# 2022-11-04_ESP32-Cseries_Riser.net
KiCad netlist of a schematic drawn in EasyEDA
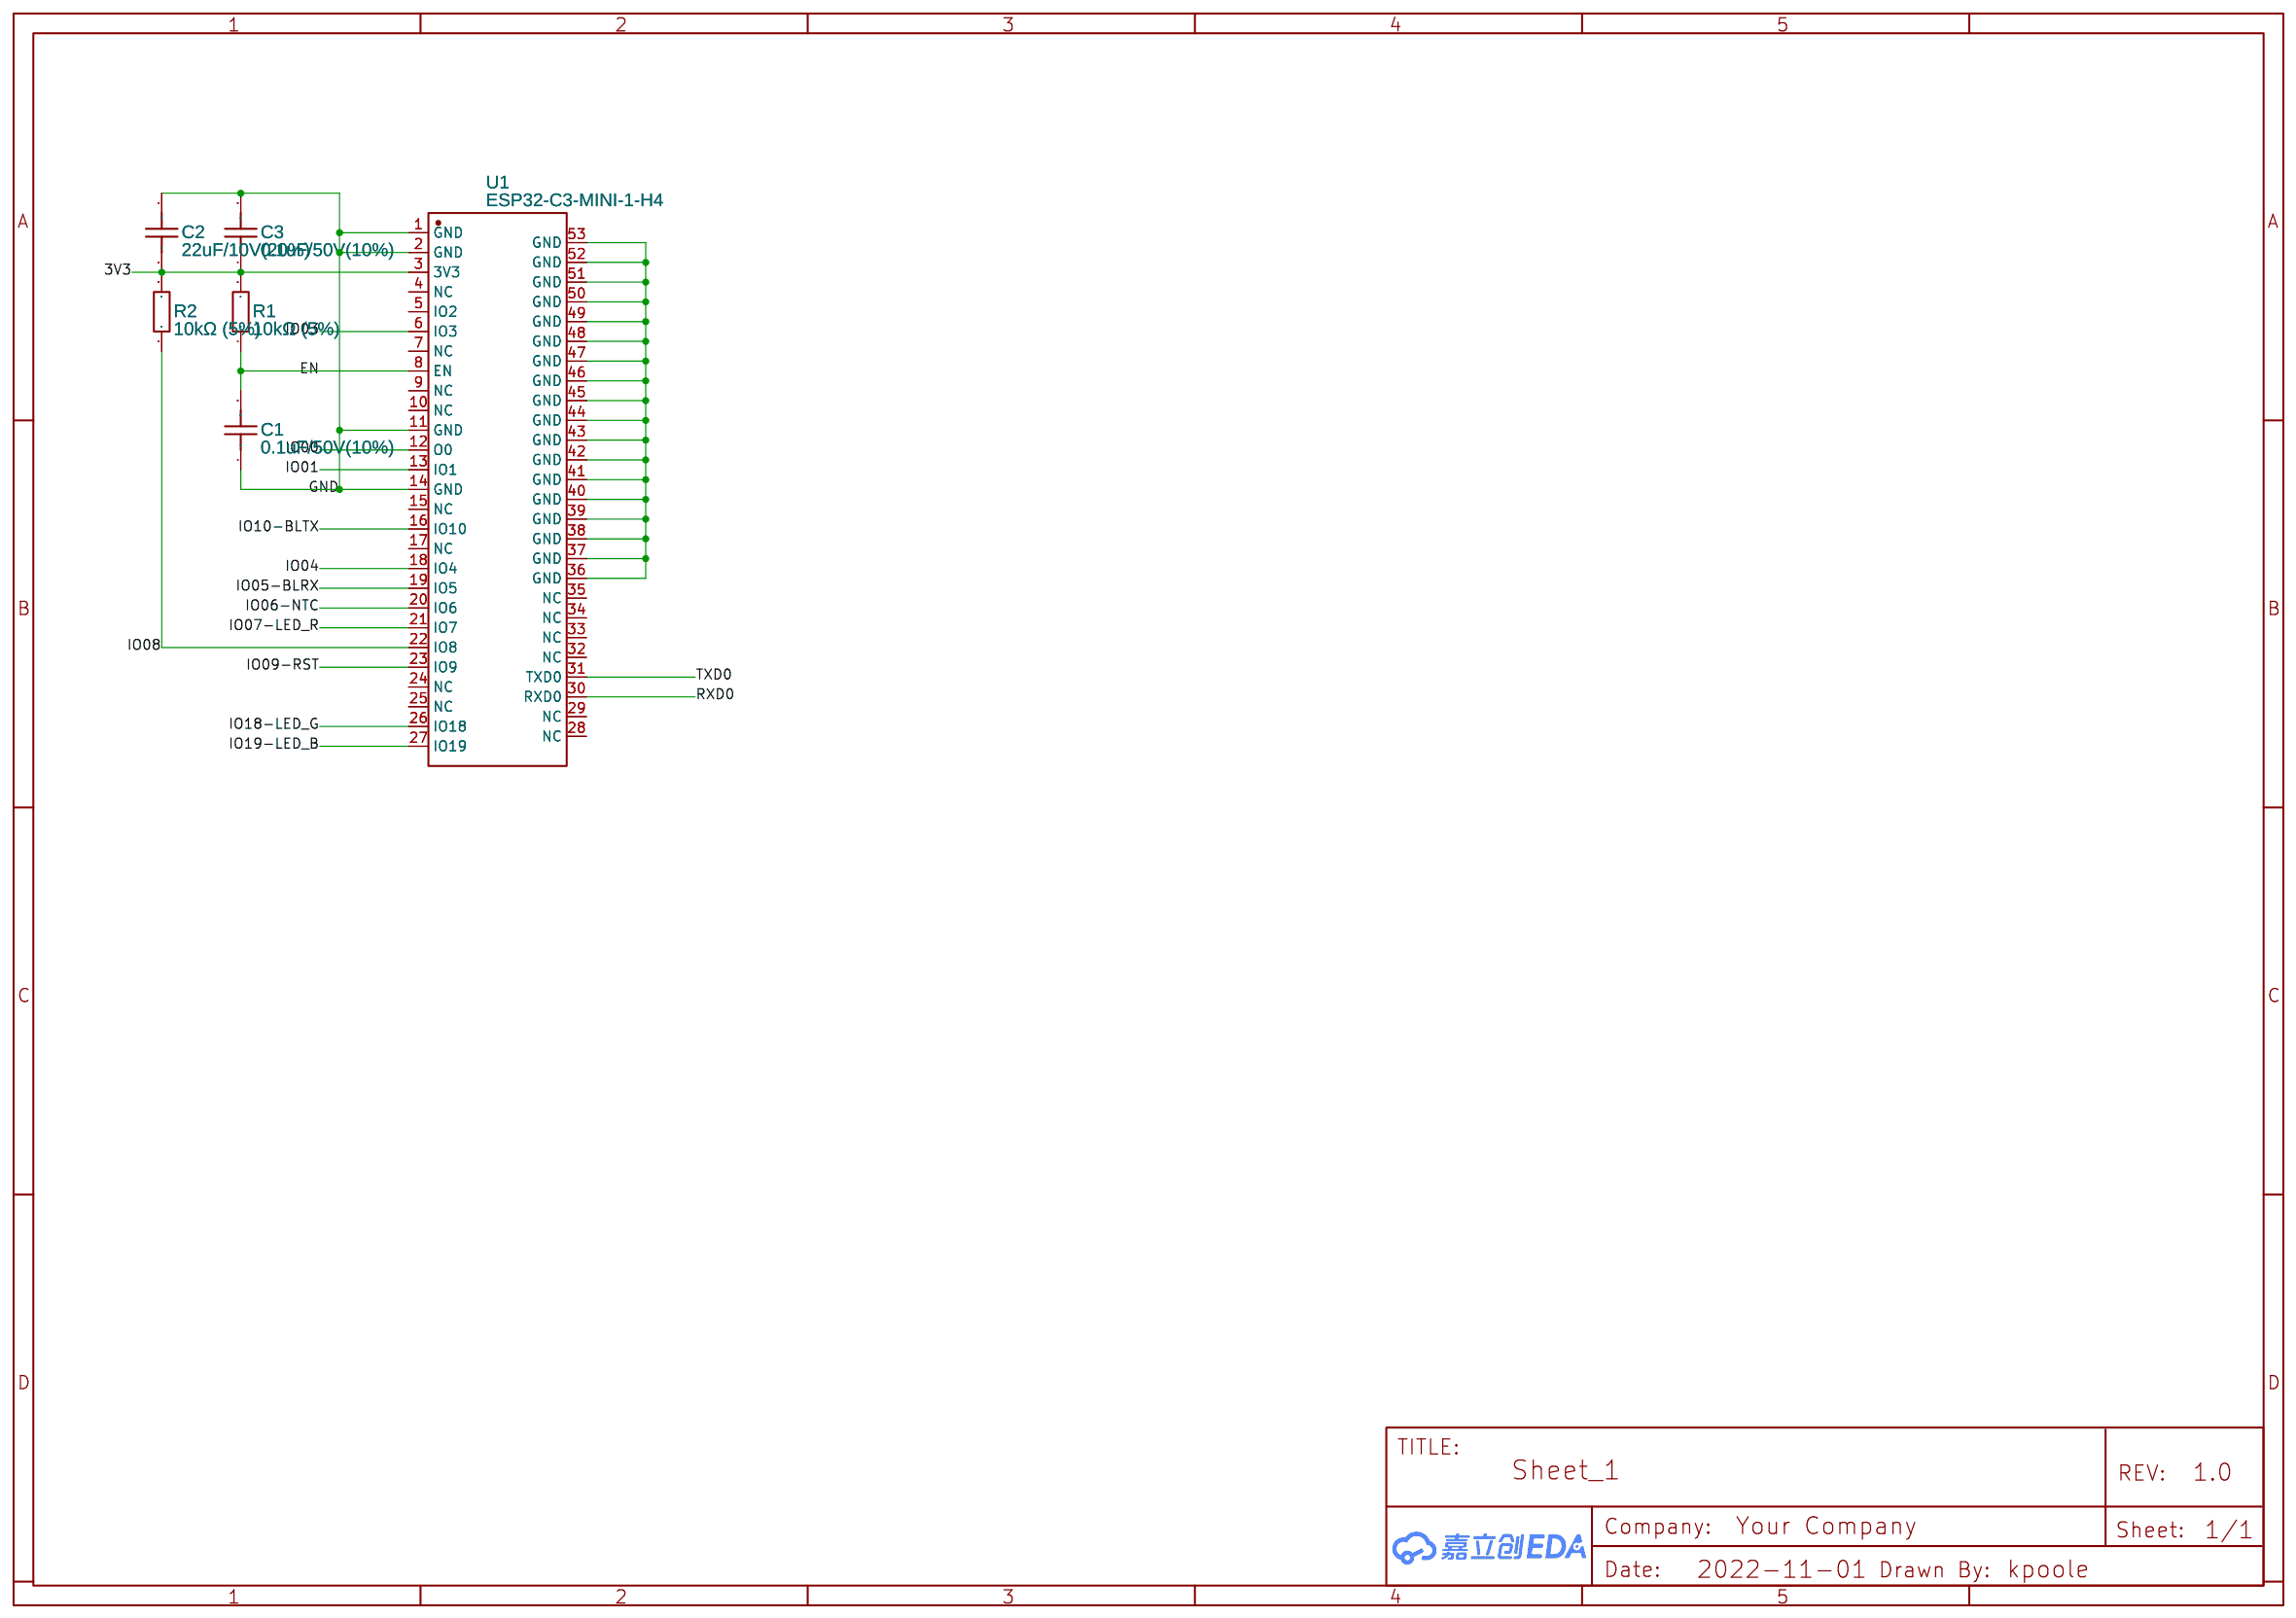
[diagram p0: schematic sheet]

(export (version "E")
  (design (tool "Eeschema 10.0.6"))
  (components
    (comp (ref "C1")
      (value "0.1uF/50V(10%)")
      (fields
        (field (name "BOM_Manufacturer Part") "0603BB104K500NGT")
        (field (name "BOM_Supplier Part") "C2168571")
      )
      (libsource (lib "") (part "0603BB104K500NGT"))
    )
    (comp (ref "C2")
      (value "22uF/10V(20%)")
      (fields
        (field (name "BOM_Manufacturer Part") "CL10A226MP8NUNE")
        (field (name "BOM_Supplier Part") "C86295")
      )
      (libsource (lib "") (part "CL10A226MP8NUNE"))
    )
    (comp (ref "C3")
      (value "0.1uF/50V(10%)")
      (fields
        (field (name "BOM_Manufacturer Part") "CAP-SMD-0603-10uF-50V-10%")
        (field (name "BOM_Supplier Part") "C9900006127")
      )
      (libsource (lib "") (part "CAP-SMD-0603-10UF-50V-10%"))
    )
    (comp (ref "R1")
      (value "10kΩ (5%)")
      (fields
        (field (name "BOM_Manufacturer Part") "RK73B2ATTD103J")
        (field (name "BOM_Supplier Part") "C159912")
      )
      (libsource (lib "") (part "RK73B2ATTD103J"))
    )
    (comp (ref "R2")
      (value "10kΩ (5%)")
      (fields
        (field (name "BOM_Manufacturer Part") "RK73B2ATTD103J")
        (field (name "BOM_Supplier Part") "C159912")
      )
      (libsource (lib "") (part "RK73B2ATTD103J"))
    )
    (comp (ref "U1")
      (value "ESP32-C3-MINI-1-H4")
      (fields (field (name "BOM_Supplier Part") "C2935306"))
      (libsource (lib "") (part "ESP32-C3-MINI-1-H4"))
    )
  )
  (nets
    (net (code "1") (name "/3V3") (class "Default")
      (node (ref "C2") (pin "2") (pinfunction "2_2") (pintype "unspecified"))
      (node (ref "C3") (pin "1") (pinfunction "1_1") (pintype "unspecified"))
      (node (ref "R1") (pin "2") (pinfunction "2_2") (pintype "unspecified"))
      (node (ref "R2") (pin "2") (pinfunction "2_2") (pintype "unspecified"))
      (node (ref "U1") (pin "3") (pinfunction "3V3_3") (pintype "unspecified"))
    )
    (net (code "2") (name "/EN") (class "Default")
      (node (ref "C1") (pin "2") (pinfunction "2_2") (pintype "unspecified"))
      (node (ref "R1") (pin "1") (pinfunction "1_1") (pintype "unspecified"))
      (node (ref "U1") (pin "8") (pinfunction "EN_8") (pintype "unspecified"))
    )
    (net (code "3") (name "/GND") (class "Default")
      (node (ref "C1") (pin "1") (pinfunction "1_1") (pintype "unspecified"))
      (node (ref "C2") (pin "1") (pinfunction "1_1") (pintype "unspecified"))
      (node (ref "C3") (pin "2") (pinfunction "2_2") (pintype "unspecified"))
      (node (ref "U1") (pin "1") (pinfunction "GND_1") (pintype "unspecified"))
      (node (ref "U1") (pin "11") (pinfunction "GND_11") (pintype "unspecified"))
      (node (ref "U1") (pin "14") (pinfunction "GND_14") (pintype "unspecified"))
      (node (ref "U1") (pin "2") (pinfunction "GND_2") (pintype "unspecified"))
    )
    (net (code "4") (name "/IO00") (class "Default")
      (node (ref "U1") (pin "12") (pinfunction "O0_12") (pintype "unspecified"))
    )
    (net (code "5") (name "/IO01") (class "Default")
      (node (ref "U1") (pin "13") (pinfunction "IO1_13") (pintype "unspecified"))
    )
    (net (code "6") (name "/IO03") (class "Default")
      (node (ref "U1") (pin "6") (pinfunction "IO3_6") (pintype "unspecified"))
    )
    (net (code "7") (name "/IO04") (class "Default")
      (node (ref "U1") (pin "18") (pinfunction "IO4_18") (pintype "unspecified"))
    )
    (net (code "8") (name "/IO05-BLRX") (class "Default")
      (node (ref "U1") (pin "19") (pinfunction "IO5_19") (pintype "unspecified"))
    )
    (net (code "9") (name "/IO06-NTC") (class "Default")
      (node (ref "U1") (pin "20") (pinfunction "IO6_20") (pintype "unspecified"))
    )
    (net (code "10") (name "/IO07-LED_R") (class "Default")
      (node (ref "U1") (pin "21") (pinfunction "IO7_21") (pintype "unspecified"))
    )
    (net (code "11") (name "/IO08") (class "Default")
      (node (ref "R2") (pin "1") (pinfunction "1_1") (pintype "unspecified"))
      (node (ref "U1") (pin "22") (pinfunction "IO8_22") (pintype "unspecified"))
    )
    (net (code "12") (name "/IO09-RST") (class "Default")
      (node (ref "U1") (pin "23") (pinfunction "IO9_23") (pintype "unspecified"))
    )
    (net (code "13") (name "/IO10-BLTX") (class "Default")
      (node (ref "U1") (pin "16") (pinfunction "IO10_16") (pintype "unspecified"))
    )
    (net (code "14") (name "/IO18-LED_G") (class "Default")
      (node (ref "U1") (pin "26") (pinfunction "IO18_26") (pintype "unspecified"))
    )
    (net (code "15") (name "/IO19-LED_B") (class "Default")
      (node (ref "U1") (pin "27") (pinfunction "IO19_27") (pintype "unspecified"))
    )
    (net (code "16") (name "/RXD0") (class "Default")
      (node (ref "U1") (pin "30") (pinfunction "RXD0_30") (pintype "unspecified"))
    )
    (net (code "17") (name "/TXD0") (class "Default")
      (node (ref "U1") (pin "31") (pinfunction "TXD0_31") (pintype "unspecified"))
    )
    (net (code "18") (name "Net-(U1-GND-Pad36)") (class "Default")
      (node (ref "U1") (pin "36") (pinfunction "GND_36") (pintype "unspecified"))
      (node (ref "U1") (pin "37") (pinfunction "GND_37") (pintype "unspecified"))
      (node (ref "U1") (pin "38") (pinfunction "GND_38") (pintype "unspecified"))
      (node (ref "U1") (pin "39") (pinfunction "GND_39") (pintype "unspecified"))
      (node (ref "U1") (pin "40") (pinfunction "GND_40") (pintype "unspecified"))
      (node (ref "U1") (pin "41") (pinfunction "GND_41") (pintype "unspecified"))
      (node (ref "U1") (pin "42") (pinfunction "GND_42") (pintype "unspecified"))
      (node (ref "U1") (pin "43") (pinfunction "GND_43") (pintype "unspecified"))
      (node (ref "U1") (pin "44") (pinfunction "GND_44") (pintype "unspecified"))
      (node (ref "U1") (pin "45") (pinfunction "GND_45") (pintype "unspecified"))
      (node (ref "U1") (pin "46") (pinfunction "GND_46") (pintype "unspecified"))
      (node (ref "U1") (pin "47") (pinfunction "GND_47") (pintype "unspecified"))
      (node (ref "U1") (pin "48") (pinfunction "GND_48") (pintype "unspecified"))
      (node (ref "U1") (pin "49") (pinfunction "GND_49") (pintype "unspecified"))
      (node (ref "U1") (pin "50") (pinfunction "GND_50") (pintype "unspecified"))
      (node (ref "U1") (pin "51") (pinfunction "GND_51") (pintype "unspecified"))
      (node (ref "U1") (pin "52") (pinfunction "GND_52") (pintype "unspecified"))
      (node (ref "U1") (pin "53") (pinfunction "GND_53") (pintype "unspecified"))
    )
    (net (code "19") (name "unconnected-(U1-IO2-Pad5)") (class "Default")
      (node (ref "U1") (pin "5") (pinfunction "IO2_5") (pintype "unspecified"))
    )
    (net (code "20") (name "unconnected-(U1-NC-Pad4)") (class "Default")
      (node (ref "U1") (pin "4") (pinfunction "NC_4") (pintype "unspecified"))
    )
    (net (code "21") (name "unconnected-(U1-NC-Pad7)") (class "Default")
      (node (ref "U1") (pin "7") (pinfunction "NC_7") (pintype "unspecified"))
    )
    (net (code "22") (name "unconnected-(U1-NC-Pad9)") (class "Default")
      (node (ref "U1") (pin "9") (pinfunction "NC_9") (pintype "unspecified"))
    )
    (net (code "23") (name "unconnected-(U1-NC-Pad10)") (class "Default")
      (node (ref "U1") (pin "10") (pinfunction "NC_10") (pintype "unspecified"))
    )
    (net (code "24") (name "unconnected-(U1-NC-Pad15)") (class "Default")
      (node (ref "U1") (pin "15") (pinfunction "NC_15") (pintype "unspecified"))
    )
    (net (code "25") (name "unconnected-(U1-NC-Pad17)") (class "Default")
      (node (ref "U1") (pin "17") (pinfunction "NC_17") (pintype "unspecified"))
    )
    (net (code "26") (name "unconnected-(U1-NC-Pad24)") (class "Default")
      (node (ref "U1") (pin "24") (pinfunction "NC_24") (pintype "unspecified"))
    )
    (net (code "27") (name "unconnected-(U1-NC-Pad25)") (class "Default")
      (node (ref "U1") (pin "25") (pinfunction "NC_25") (pintype "unspecified"))
    )
    (net (code "28") (name "unconnected-(U1-NC-Pad28)") (class "Default")
      (node (ref "U1") (pin "28") (pinfunction "NC_28") (pintype "unspecified"))
    )
    (net (code "29") (name "unconnected-(U1-NC-Pad29)") (class "Default")
      (node (ref "U1") (pin "29") (pinfunction "NC_29") (pintype "unspecified"))
    )
    (net (code "30") (name "unconnected-(U1-NC-Pad32)") (class "Default")
      (node (ref "U1") (pin "32") (pinfunction "NC_32") (pintype "unspecified"))
    )
    (net (code "31") (name "unconnected-(U1-NC-Pad33)") (class "Default")
      (node (ref "U1") (pin "33") (pinfunction "NC_33") (pintype "unspecified"))
    )
    (net (code "32") (name "unconnected-(U1-NC-Pad34)") (class "Default")
      (node (ref "U1") (pin "34") (pinfunction "NC_34") (pintype "unspecified"))
    )
    (net (code "33") (name "unconnected-(U1-NC-Pad35)") (class "Default")
      (node (ref "U1") (pin "35") (pinfunction "NC_35") (pintype "unspecified"))
    )
  )
)
